# FTDI.net
KiCad netlist of a schematic drawn in Altium Designer
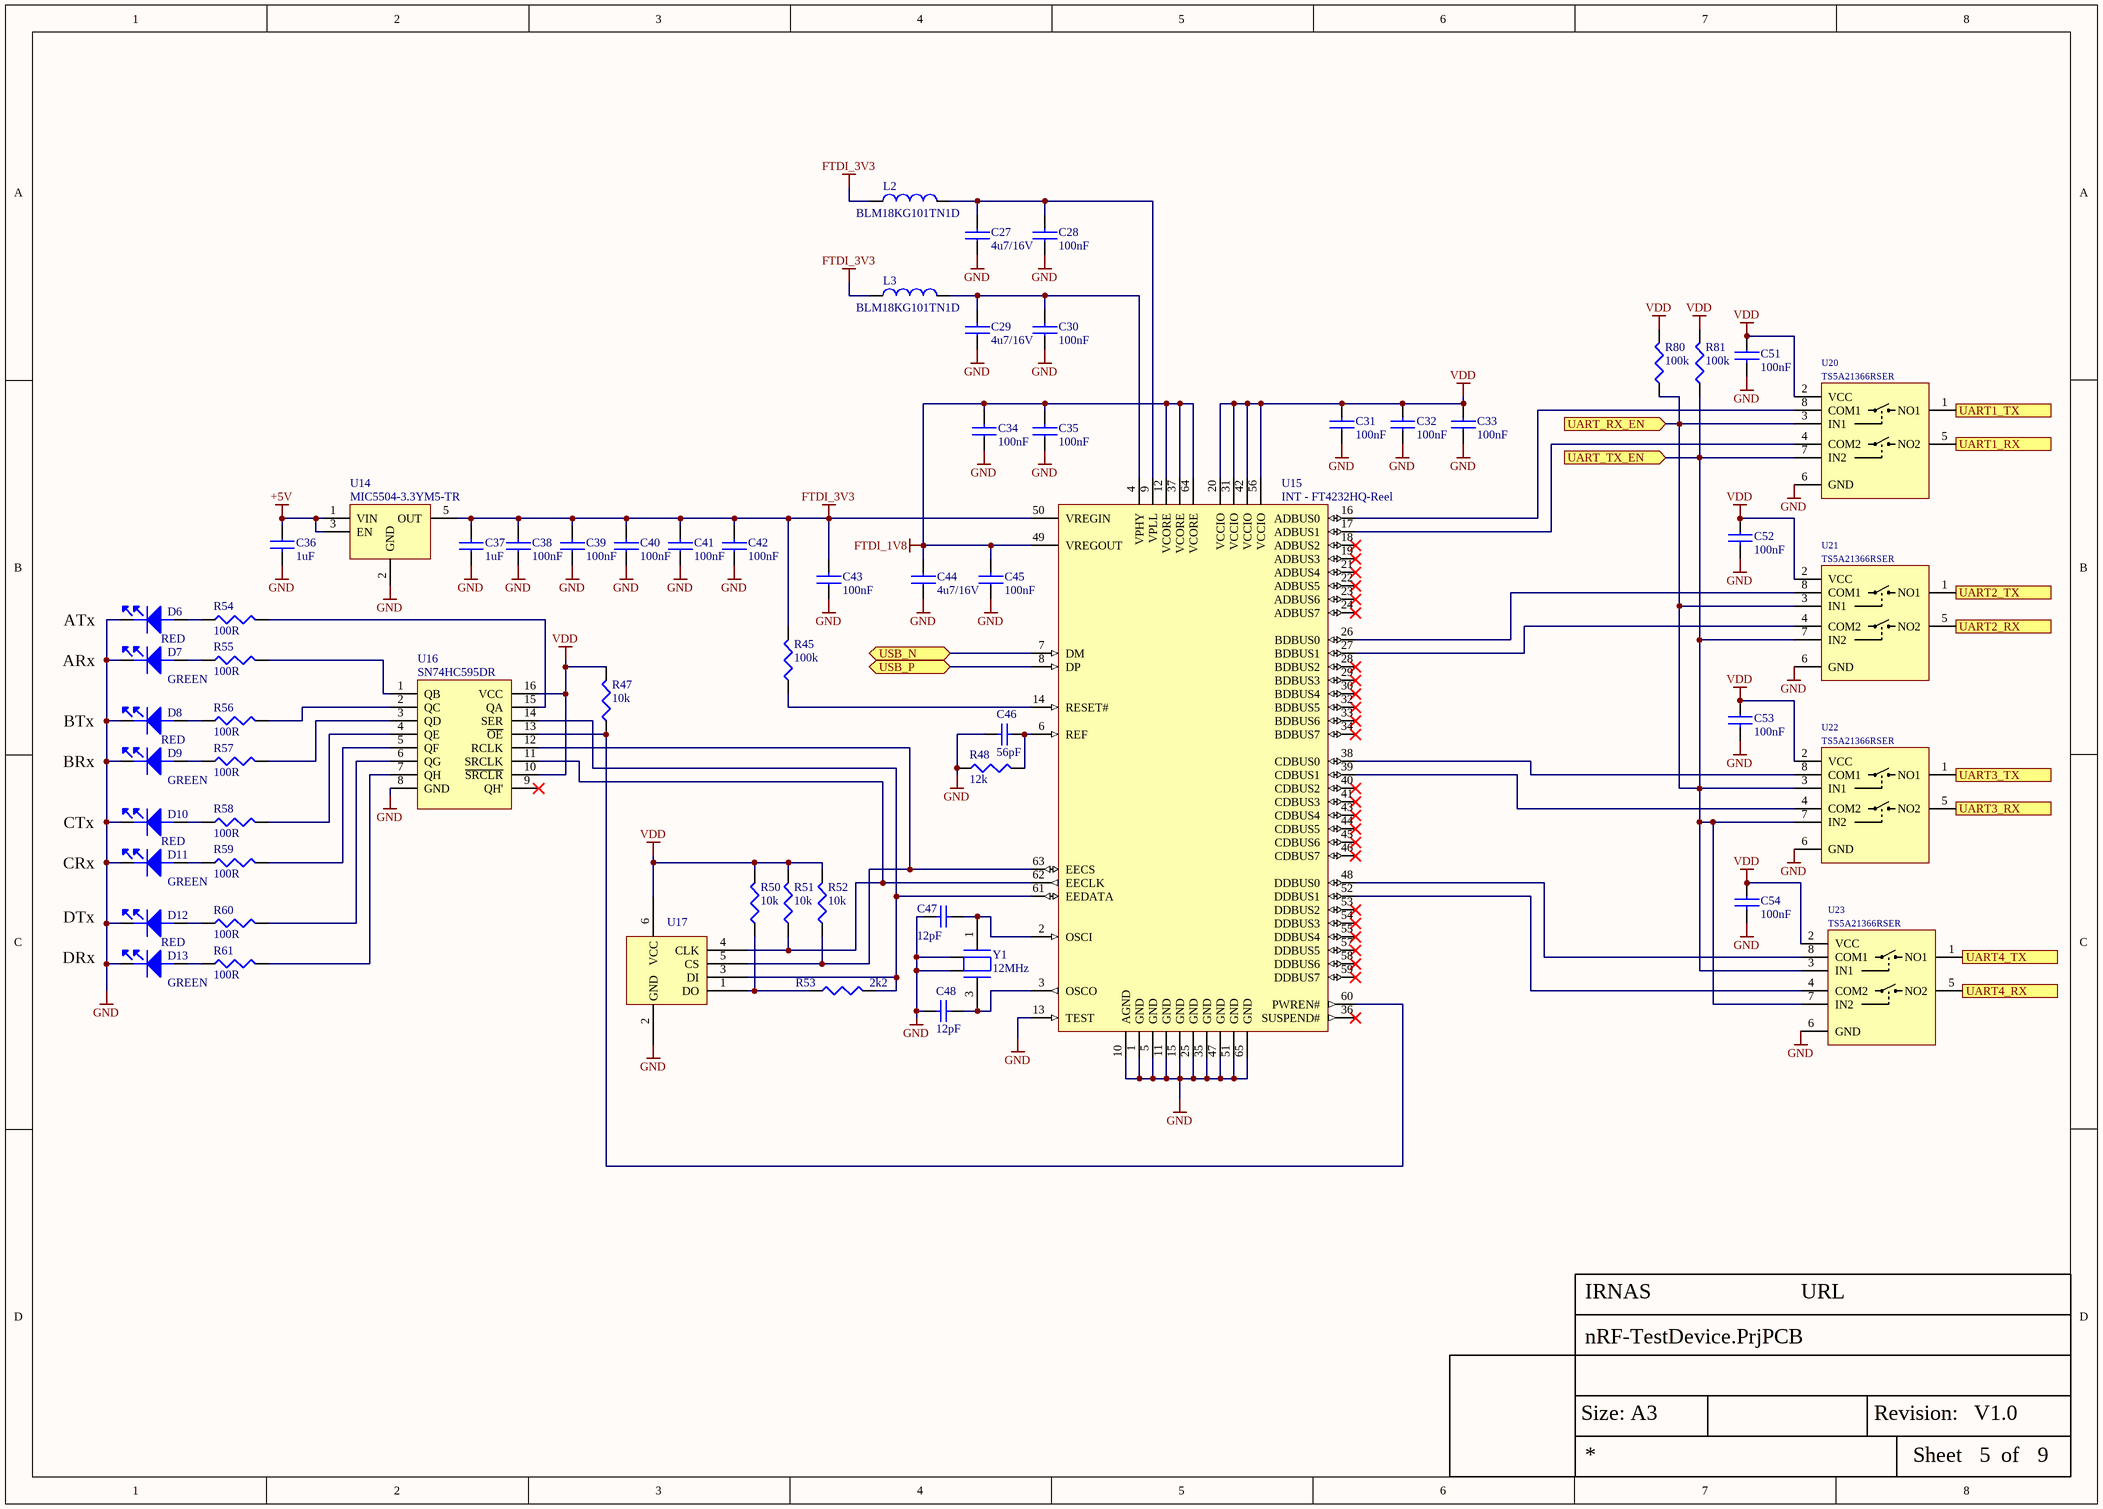
[diagram p0: FTDI.SchDoc]

(export (version "E")
  (design (tool "Eeschema 10.0.6"))
  (components
    (comp (ref "C27")
      (value "4u7/16V")
      (footprint "CAP0603")
      (description "MURATA - GRM188R61C475KAAJD - CAP, MLCC, X5R, 4.7UF, 16V, 0603")
      (fields
        (field (name "MANUFACTURER") "MURATA")
        (field (name "MANUFACTURER PART NUMBER") "GRM188R61C475KAAJD")
      )
      (libsource (lib "Passive") (part "C - 4u7  16V 0603"))
    )
    (comp (ref "C28")
      (value "100nF")
      (footprint "CAP0402")
      (fields
        (field (name "MANUFACTURER") "Multicomp")
        (field (name "MANUFACTURER PART NUMBER") "MC0402X104J160CT")
        (field (name "TOLERANCE") "5%")
      )
      (libsource (lib "Passive") (part "C - 100nF/0402"))
    )
    (comp (ref "C29")
      (value "4u7/16V")
      (footprint "CAP0603")
      (description "MURATA - GRM188R61C475KAAJD - CAP, MLCC, X5R, 4.7UF, 16V, 0603")
      (fields
        (field (name "MANUFACTURER") "MURATA")
        (field (name "MANUFACTURER PART NUMBER") "GRM188R61C475KAAJD")
      )
      (libsource (lib "Passive") (part "C - 4u7  16V 0603"))
    )
    (comp (ref "C30")
      (value "100nF")
      (footprint "CAP0402")
      (fields
        (field (name "MANUFACTURER") "Multicomp")
        (field (name "MANUFACTURER PART NUMBER") "MC0402X104J160CT")
        (field (name "TOLERANCE") "5%")
      )
      (libsource (lib "Passive") (part "C - 100nF/0402"))
    )
    (comp (ref "C31")
      (value "100nF")
      (footprint "CAP0402")
      (fields
        (field (name "MANUFACTURER") "Multicomp")
        (field (name "MANUFACTURER PART NUMBER") "MC0402X104J160CT")
        (field (name "TOLERANCE") "5%")
      )
      (libsource (lib "Passive") (part "C - 100nF/0402"))
    )
    (comp (ref "C32")
      (value "100nF")
      (footprint "CAP0402")
      (fields
        (field (name "MANUFACTURER") "Multicomp")
        (field (name "MANUFACTURER PART NUMBER") "MC0402X104J160CT")
        (field (name "TOLERANCE") "5%")
      )
      (libsource (lib "Passive") (part "C - 100nF/0402"))
    )
    (comp (ref "C33")
      (value "100nF")
      (footprint "CAP0402")
      (fields
        (field (name "MANUFACTURER") "Multicomp")
        (field (name "MANUFACTURER PART NUMBER") "MC0402X104J160CT")
        (field (name "TOLERANCE") "5%")
      )
      (libsource (lib "Passive") (part "C - 100nF/0402"))
    )
    (comp (ref "C34")
      (value "100nF")
      (footprint "CAP0402")
      (fields
        (field (name "MANUFACTURER") "Multicomp")
        (field (name "MANUFACTURER PART NUMBER") "MC0402X104J160CT")
        (field (name "TOLERANCE") "5%")
      )
      (libsource (lib "Passive") (part "C - 100nF/0402"))
    )
    (comp (ref "C35")
      (value "100nF")
      (footprint "CAP0402")
      (fields
        (field (name "MANUFACTURER") "Multicomp")
        (field (name "MANUFACTURER PART NUMBER") "MC0402X104J160CT")
        (field (name "TOLERANCE") "5%")
      )
      (libsource (lib "Passive") (part "C - 100nF/0402"))
    )
    (comp (ref "C36")
      (value "1uF")
      (footprint "CAP0402")
      (description "CAP CER 1UF 10V 20% X5R 0402")
      (fields
        (field (name "MANUFACTURER") "Murata")
        (field (name "MANUFACTURER PART NUMBER") "GRM155R61A105ME15D")
      )
      (libsource (lib "Passive") (part "C - 1uF/0402"))
    )
    (comp (ref "C37")
      (value "1uF")
      (footprint "CAP0402")
      (description "CAP CER 1UF 10V 20% X5R 0402")
      (fields
        (field (name "MANUFACTURER") "Murata")
        (field (name "MANUFACTURER PART NUMBER") "GRM155R61A105ME15D")
      )
      (libsource (lib "Passive") (part "C - 1uF/0402"))
    )
    (comp (ref "C38")
      (value "100nF")
      (footprint "CAP0402")
      (fields
        (field (name "MANUFACTURER") "Multicomp")
        (field (name "MANUFACTURER PART NUMBER") "MC0402X104J160CT")
        (field (name "TOLERANCE") "5%")
      )
      (libsource (lib "Passive") (part "C - 100nF/0402"))
    )
    (comp (ref "C39")
      (value "100nF")
      (footprint "CAP0402")
      (fields
        (field (name "MANUFACTURER") "Multicomp")
        (field (name "MANUFACTURER PART NUMBER") "MC0402X104J160CT")
        (field (name "TOLERANCE") "5%")
      )
      (libsource (lib "Passive") (part "C - 100nF/0402"))
    )
    (comp (ref "C40")
      (value "100nF")
      (footprint "CAP0402")
      (fields
        (field (name "MANUFACTURER") "Multicomp")
        (field (name "MANUFACTURER PART NUMBER") "MC0402X104J160CT")
        (field (name "TOLERANCE") "5%")
      )
      (libsource (lib "Passive") (part "C - 100nF/0402"))
    )
    (comp (ref "C41")
      (value "100nF")
      (footprint "CAP0402")
      (fields
        (field (name "MANUFACTURER") "Multicomp")
        (field (name "MANUFACTURER PART NUMBER") "MC0402X104J160CT")
        (field (name "TOLERANCE") "5%")
      )
      (libsource (lib "Passive") (part "C - 100nF/0402"))
    )
    (comp (ref "C42")
      (value "100nF")
      (footprint "CAP0402")
      (fields
        (field (name "MANUFACTURER") "Multicomp")
        (field (name "MANUFACTURER PART NUMBER") "MC0402X104J160CT")
        (field (name "TOLERANCE") "5%")
      )
      (libsource (lib "Passive") (part "C - 100nF/0402"))
    )
    (comp (ref "C43")
      (value "100nF")
      (footprint "CAP0402")
      (fields
        (field (name "MANUFACTURER") "Multicomp")
        (field (name "MANUFACTURER PART NUMBER") "MC0402X104J160CT")
        (field (name "TOLERANCE") "5%")
      )
      (libsource (lib "Passive") (part "C - 100nF/0402"))
    )
    (comp (ref "C44")
      (value "4u7/16V")
      (footprint "CAP0603")
      (description "MURATA - GRM188R61C475KAAJD - CAP, MLCC, X5R, 4.7UF, 16V, 0603")
      (fields
        (field (name "MANUFACTURER") "MURATA")
        (field (name "MANUFACTURER PART NUMBER") "GRM188R61C475KAAJD")
      )
      (libsource (lib "Passive") (part "C - 4u7  16V 0603"))
    )
    (comp (ref "C45")
      (value "100nF")
      (footprint "CAP0402")
      (fields
        (field (name "MANUFACTURER") "Multicomp")
        (field (name "MANUFACTURER PART NUMBER") "MC0402X104J160CT")
        (field (name "TOLERANCE") "5%")
      )
      (libsource (lib "Passive") (part "C - 100nF/0402"))
    )
    (comp (ref "C46")
      (value "56pF")
      (footprint "CAP0402")
      (description "CAP CER 56PF 50V C0G/NP0 0402")
      (fields (field (name "Comment") "56pF/50V/0402") (field (name "PUBLISHER") "Altium Limited"))
      (libsource (lib "Passive") (part "C - 56pF/50V/0402"))
    )
    (comp (ref "C47")
      (value "12pF")
      (footprint "CAP0402")
      (description "CAP CER 12PF 50V C0G/NP0 0402")
      (fields (field (name "Comment") "12pF/50V/0402") (field (name "PUBLISHER") "Altium Limited"))
      (libsource (lib "Passive") (part "C - 12pF/50V/0402"))
    )
    (comp (ref "C48")
      (value "12pF")
      (footprint "CAP0402")
      (description "CAP CER 12PF 50V C0G/NP0 0402")
      (fields (field (name "Comment") "12pF/50V/0402") (field (name "PUBLISHER") "Altium Limited"))
      (libsource (lib "Passive") (part "C - 12pF/50V/0402"))
    )
    (comp (ref "C51")
      (value "100nF")
      (footprint "CAP0402")
      (fields
        (field (name "MANUFACTURER") "Multicomp")
        (field (name "MANUFACTURER PART NUMBER") "MC0402X104J160CT")
        (field (name "TOLERANCE") "5%")
      )
      (libsource (lib "Passive") (part "C - 100nF/0402"))
    )
    (comp (ref "C52")
      (value "100nF")
      (footprint "CAP0402")
      (fields
        (field (name "MANUFACTURER") "Multicomp")
        (field (name "MANUFACTURER PART NUMBER") "MC0402X104J160CT")
        (field (name "TOLERANCE") "5%")
      )
      (libsource (lib "Passive") (part "C - 100nF/0402"))
    )
    (comp (ref "C53")
      (value "100nF")
      (footprint "CAP0402")
      (fields
        (field (name "MANUFACTURER") "Multicomp")
        (field (name "MANUFACTURER PART NUMBER") "MC0402X104J160CT")
        (field (name "TOLERANCE") "5%")
      )
      (libsource (lib "Passive") (part "C - 100nF/0402"))
    )
    (comp (ref "C54")
      (value "100nF")
      (footprint "CAP0402")
      (fields
        (field (name "MANUFACTURER") "Multicomp")
        (field (name "MANUFACTURER PART NUMBER") "MC0402X104J160CT")
        (field (name "TOLERANCE") "5%")
      )
      (libsource (lib "Passive") (part "C - 100nF/0402"))
    )
    (comp (ref "D6")
      (value "LED RED")
      (footprint "LED0603")
      (description "BROADCOM LIMITED - HSMS-C190 - LED, RED, 10MCD, 626NM")
      (fields
        (field (name "MANUFACTURER") "BROADCOM LIMITED")
        (field (name "MANUFACTURER PART NUMBER") "HSMS-C190")
      )
      (libsource (lib "Active") (part "LED - LED RED"))
    )
    (comp (ref "D7")
      (value "LED GREEN")
      (footprint "LED0603")
      (description "HSME-C191 -  LED, Green, SMD, 0603, 20 mA, 2.1 V, 572 nm")
      (fields
        (field (name "MANUFACTURER") "BROADCOM LIMITED")
        (field (name "MANUFACTURER PART NUMBER") "HSMS-C190")
      )
      (libsource (lib "Active") (part "LED - LED GREEN"))
    )
    (comp (ref "D8")
      (value "LED RED")
      (footprint "LED0603")
      (description "BROADCOM LIMITED - HSMS-C190 - LED, RED, 10MCD, 626NM")
      (fields
        (field (name "MANUFACTURER") "BROADCOM LIMITED")
        (field (name "MANUFACTURER PART NUMBER") "HSMS-C190")
      )
      (libsource (lib "Active") (part "LED - LED RED"))
    )
    (comp (ref "D9")
      (value "LED GREEN")
      (footprint "LED0603")
      (description "HSME-C191 -  LED, Green, SMD, 0603, 20 mA, 2.1 V, 572 nm")
      (fields
        (field (name "MANUFACTURER") "BROADCOM LIMITED")
        (field (name "MANUFACTURER PART NUMBER") "HSMS-C190")
      )
      (libsource (lib "Active") (part "LED - LED GREEN"))
    )
    (comp (ref "D10")
      (value "LED RED")
      (footprint "LED0603")
      (description "BROADCOM LIMITED - HSMS-C190 - LED, RED, 10MCD, 626NM")
      (fields
        (field (name "MANUFACTURER") "BROADCOM LIMITED")
        (field (name "MANUFACTURER PART NUMBER") "HSMS-C190")
      )
      (libsource (lib "Active") (part "LED - LED RED"))
    )
    (comp (ref "D11")
      (value "LED GREEN")
      (footprint "LED0603")
      (description "HSME-C191 -  LED, Green, SMD, 0603, 20 mA, 2.1 V, 572 nm")
      (fields
        (field (name "MANUFACTURER") "BROADCOM LIMITED")
        (field (name "MANUFACTURER PART NUMBER") "HSMS-C190")
      )
      (libsource (lib "Active") (part "LED - LED GREEN"))
    )
    (comp (ref "D12")
      (value "LED RED")
      (footprint "LED0603")
      (description "BROADCOM LIMITED - HSMS-C190 - LED, RED, 10MCD, 626NM")
      (fields
        (field (name "MANUFACTURER") "BROADCOM LIMITED")
        (field (name "MANUFACTURER PART NUMBER") "HSMS-C190")
      )
      (libsource (lib "Active") (part "LED - LED RED"))
    )
    (comp (ref "D13")
      (value "LED GREEN")
      (footprint "LED0603")
      (description "HSME-C191 -  LED, Green, SMD, 0603, 20 mA, 2.1 V, 572 nm")
      (fields
        (field (name "MANUFACTURER") "BROADCOM LIMITED")
        (field (name "MANUFACTURER PART NUMBER") "HSMS-C190")
      )
      (libsource (lib "Active") (part "LED - LED GREEN"))
    )
    (comp (ref "L2")
      (value "BLM18KG101TN1D")
      (footprint "IND0603")
      (description "Ferrite Bead, 0603 [1608 Metric], 100 ohm, 3 A, BLM18K Series, 0.03 ohm, ± 25%")
      (libsource (lib "Passive") (part "L - BLM18KG101TN1D"))
    )
    (comp (ref "L3")
      (value "BLM18KG101TN1D")
      (footprint "IND0603")
      (description "Ferrite Bead, 0603 [1608 Metric], 100 ohm, 3 A, BLM18K Series, 0.03 ohm, ± 25%")
      (libsource (lib "Passive") (part "L - BLM18KG101TN1D"))
    )
    (comp (ref "R45")
      (value "100k")
      (footprint "RES0402")
      (description "MULTICOMP   MCWR04X1003FTL   RES, THICK FILM, 100KOHM, 1%, 0.0625W")
      (fields
        (field (name "MANUFACTURER") "Multicomp")
        (field (name "MANUFACTURER PART NUMBER") "MCWR04X1003FTL")
      )
      (libsource (lib "Passive") (part "R - 100k/0402"))
    )
    (comp (ref "R47")
      (value "10k")
      (footprint "RES0402")
      (fields
        (field (name "MANUFACTURER") "Multicomp")
        (field (name "MANUFACTURER PART NUMBER") "MCWR04X1002FTL")
        (field (name "TOLERANCE") "1%")
      )
      (libsource (lib "Passive") (part "R - 10k/0402"))
    )
    (comp (ref "R48")
      (value "12k")
      (footprint "RES0402")
      (fields
        (field (name "MANUFACTURER") "Multicomp")
        (field (name "MANUFACTURER PART NUMBER") "MCWR04X1202FTL")
        (field (name "TOLERANCE") "1%")
      )
      (libsource (lib "Passive") (part "R - 12k/0402"))
    )
    (comp (ref "R50")
      (value "10k")
      (footprint "RES0402")
      (fields
        (field (name "MANUFACTURER") "Multicomp")
        (field (name "MANUFACTURER PART NUMBER") "MCWR04X1002FTL")
        (field (name "TOLERANCE") "1%")
      )
      (libsource (lib "Passive") (part "R - 10k/0402"))
    )
    (comp (ref "R51")
      (value "10k")
      (footprint "RES0402")
      (fields
        (field (name "MANUFACTURER") "Multicomp")
        (field (name "MANUFACTURER PART NUMBER") "MCWR04X1002FTL")
        (field (name "TOLERANCE") "1%")
      )
      (libsource (lib "Passive") (part "R - 10k/0402"))
    )
    (comp (ref "R52")
      (value "10k")
      (footprint "RES0402")
      (fields
        (field (name "MANUFACTURER") "Multicomp")
        (field (name "MANUFACTURER PART NUMBER") "MCWR04X1002FTL")
        (field (name "TOLERANCE") "1%")
      )
      (libsource (lib "Passive") (part "R - 10k/0402"))
    )
    (comp (ref "R53")
      (value "2k2")
      (footprint "RES0402")
      (description "SMD Chip Resistor, 2.2 kohm, ± 1%, 62.5 mW, 0402 [1005 Metric], Thick Film, General Purpose")
      (libsource (lib "Passive") (part "R - 2k2/0402"))
    )
    (comp (ref "R54")
      (value "100R")
      (footprint "RES0402")
      (fields
        (field (name "MANUFACTURER") "Multicomp")
        (field (name "MANUFACTURER PART NUMBER") "MCMR04X1000FTL")
        (field (name "TOLERANCE") "1%")
      )
      (libsource (lib "Passive") (part "R - 100R/0402"))
    )
    (comp (ref "R55")
      (value "100R")
      (footprint "RES0402")
      (fields
        (field (name "MANUFACTURER") "Multicomp")
        (field (name "MANUFACTURER PART NUMBER") "MCMR04X1000FTL")
        (field (name "TOLERANCE") "1%")
      )
      (libsource (lib "Passive") (part "R - 100R/0402"))
    )
    (comp (ref "R56")
      (value "100R")
      (footprint "RES0402")
      (fields
        (field (name "MANUFACTURER") "Multicomp")
        (field (name "MANUFACTURER PART NUMBER") "MCMR04X1000FTL")
        (field (name "TOLERANCE") "1%")
      )
      (libsource (lib "Passive") (part "R - 100R/0402"))
    )
    (comp (ref "R57")
      (value "100R")
      (footprint "RES0402")
      (fields
        (field (name "MANUFACTURER") "Multicomp")
        (field (name "MANUFACTURER PART NUMBER") "MCMR04X1000FTL")
        (field (name "TOLERANCE") "1%")
      )
      (libsource (lib "Passive") (part "R - 100R/0402"))
    )
    (comp (ref "R58")
      (value "100R")
      (footprint "RES0402")
      (fields
        (field (name "MANUFACTURER") "Multicomp")
        (field (name "MANUFACTURER PART NUMBER") "MCMR04X1000FTL")
        (field (name "TOLERANCE") "1%")
      )
      (libsource (lib "Passive") (part "R - 100R/0402"))
    )
    (comp (ref "R59")
      (value "100R")
      (footprint "RES0402")
      (fields
        (field (name "MANUFACTURER") "Multicomp")
        (field (name "MANUFACTURER PART NUMBER") "MCMR04X1000FTL")
        (field (name "TOLERANCE") "1%")
      )
      (libsource (lib "Passive") (part "R - 100R/0402"))
    )
    (comp (ref "R60")
      (value "100R")
      (footprint "RES0402")
      (fields
        (field (name "MANUFACTURER") "Multicomp")
        (field (name "MANUFACTURER PART NUMBER") "MCMR04X1000FTL")
        (field (name "TOLERANCE") "1%")
      )
      (libsource (lib "Passive") (part "R - 100R/0402"))
    )
    (comp (ref "R61")
      (value "100R")
      (footprint "RES0402")
      (fields
        (field (name "MANUFACTURER") "Multicomp")
        (field (name "MANUFACTURER PART NUMBER") "MCMR04X1000FTL")
        (field (name "TOLERANCE") "1%")
      )
      (libsource (lib "Passive") (part "R - 100R/0402"))
    )
    (comp (ref "R80")
      (value "100k")
      (footprint "RES0402")
      (description "MULTICOMP   MCWR04X1003FTL   RES, THICK FILM, 100KOHM, 1%, 0.0625W")
      (fields
        (field (name "MANUFACTURER") "Multicomp")
        (field (name "MANUFACTURER PART NUMBER") "MCWR04X1003FTL")
      )
      (libsource (lib "Passive") (part "R - 100k/0402"))
    )
    (comp (ref "R81")
      (value "100k")
      (footprint "RES0402")
      (description "MULTICOMP   MCWR04X1003FTL   RES, THICK FILM, 100KOHM, 1%, 0.0625W")
      (fields
        (field (name "MANUFACTURER") "Multicomp")
        (field (name "MANUFACTURER PART NUMBER") "MCWR04X1003FTL")
      )
      (libsource (lib "Passive") (part "R - 100k/0402"))
    )
    (comp (ref "U14")
      (value "MIC5504-3.3YM5-TR")
      (footprint "SOT23-5")
      (description "Fixed LDO Voltage Regulator, 2.5V to 5.5V, 160mV Dropout, 3.3Vout, 300mAout, SOT-23-5")
      (fields
        (field (name "MANUFACTURER") "ON SEMICONDUCTOR")
        (field (name "MANUFACTURER PART NUMBER") "LM2596DSADJG")
      )
      (libsource (lib "Active") (part "V_LIN - MIC5504-3.3YM5-TR"))
    )
    (comp (ref "U15")
      (value "INT - FT4232HQ-Reel")
      (footprint "QFN64_2_N")
      (description "Quad High Speed USB To Multipurpose UART/MPSSE IC, 64-pin QFN, Tape and Reel")
      (fields (field (name "MANUFACTURER") "FTDI") (field (name "PARTNUMBER") "FT4232HQ-Reel"))
      (libsource (lib "Active") (part "INT - FT4232HQ-Reel"))
    )
    (comp (ref "U16")
      (value "SN74HC595DR")
      (footprint "SOIC-16")
      (description "Shift Register, 74HC595, Serial to Parallel, 1 Element, 8 bit, SOIC, 16 Pins")
      (libsource (lib "Active") (part "INT - SN74HC595DR"))
    )
    (comp (ref "U17")
      (value "93LC56BT-E/OT")
      (footprint "SOT95P270X145-6N")
      (description "2K,  128 X 16,  SERIAL EE,   EXT6 SOT-23  T/R")
      (fields (field (name "MANUFACTURER") "Microchip"))
      (libsource (lib "Active") (part "MEM - 93LC56BT-E/OT"))
    )
    (comp (ref "U20")
      (value "TS5A21366RSER")
      (footprint "UQFN-8")
      (description "IC SWITCH DUAL SPST 8QFN")
      (libsource (lib "Active") (part "SW - TS5A21366RSER"))
    )
    (comp (ref "U21")
      (value "TS5A21366RSER")
      (footprint "UQFN-8")
      (description "IC SWITCH DUAL SPST 8QFN")
      (libsource (lib "Active") (part "SW - TS5A21366RSER"))
    )
    (comp (ref "U22")
      (value "TS5A21366RSER")
      (footprint "UQFN-8")
      (description "IC SWITCH DUAL SPST 8QFN")
      (libsource (lib "Active") (part "SW - TS5A21366RSER"))
    )
    (comp (ref "U23")
      (value "TS5A21366RSER")
      (footprint "UQFN-8")
      (description "IC SWITCH DUAL SPST 8QFN")
      (libsource (lib "Active") (part "SW - TS5A21366RSER"))
    )
    (comp (ref "Y1")
      (value "12MHz")
      (footprint "CRY2.5X2")
      (description "12MHz ±20ppm Crystal 10pF 150 Ohm -40°C ~ 85°C  Surface Mount 4-SMD, No Lead (DFN, LCC)")
      (fields
        (field (name "MANUFACTURER") "Abracon")
        (field (name "MANUFACTURER PART NUMBER") "ABM10-166-12.000MHZ-T3")
      )
      (libsource (lib "Passive") (part "X - 16MHz"))
    )
  )
  (nets
    (net (code "1") (name "+5V") (class "Default")
      (node (ref "C36") (pin "1") (pinfunction "1_1") (pintype "passive"))
      (node (ref "U14") (pin "1") (pinfunction "VIN_1") (pintype "open_collector"))
      (node (ref "U14") (pin "3") (pinfunction "EN_3") (pintype "open_collector"))
    )
    (net (code "2") (name "/UART1_RX") (class "Default")
      (node (ref "U20") (pin "5") (pinfunction "NO2_5") (pintype "passive"))
    )
    (net (code "3") (name "/UART1_TX") (class "Default")
      (node (ref "U20") (pin "1") (pinfunction "NO1_1") (pintype "passive"))
    )
    (net (code "4") (name "/UART2_RX") (class "Default")
      (node (ref "U21") (pin "5") (pinfunction "NO2_5") (pintype "passive"))
    )
    (net (code "5") (name "/UART2_TX") (class "Default")
      (node (ref "U21") (pin "1") (pinfunction "NO1_1") (pintype "passive"))
    )
    (net (code "6") (name "/UART3_RX") (class "Default")
      (node (ref "U22") (pin "5") (pinfunction "NO2_5") (pintype "passive"))
    )
    (net (code "7") (name "/UART3_TX") (class "Default")
      (node (ref "U22") (pin "1") (pinfunction "NO1_1") (pintype "passive"))
    )
    (net (code "8") (name "/UART4_RX") (class "Default")
      (node (ref "U23") (pin "5") (pinfunction "NO2_5") (pintype "passive"))
    )
    (net (code "9") (name "/UART4_TX") (class "Default")
      (node (ref "U23") (pin "1") (pinfunction "NO1_1") (pintype "passive"))
    )
    (net (code "10") (name "/UART_RX_EN") (class "Default")
      (node (ref "R80") (pin "1") (pinfunction "1_1") (pintype "passive"))
      (node (ref "R81") (pin "1") (pinfunction "1_1") (pintype "passive"))
      (node (ref "U20") (pin "3") (pinfunction "IN1_3") (pintype "passive"))
      (node (ref "U20") (pin "7") (pinfunction "IN2_7") (pintype "passive"))
      (node (ref "U21") (pin "3") (pinfunction "IN1_3") (pintype "passive"))
      (node (ref "U21") (pin "7") (pinfunction "IN2_7") (pintype "passive"))
      (node (ref "U22") (pin "3") (pinfunction "IN1_3") (pintype "passive"))
      (node (ref "U22") (pin "7") (pinfunction "IN2_7") (pintype "passive"))
      (node (ref "U23") (pin "3") (pinfunction "IN1_3") (pintype "passive"))
      (node (ref "U23") (pin "7") (pinfunction "IN2_7") (pintype "passive"))
    )
    (net (code "11") (name "/USB_N") (class "Default")
      (node (ref "U15") (pin "7") (pinfunction "DM_7") (pintype "input"))
    )
    (net (code "12") (name "/USB_P") (class "Default")
      (node (ref "U15") (pin "8") (pinfunction "DP_8") (pintype "input"))
    )
    (net (code "13") (name "FTDI_1V8") (class "Default")
      (node (ref "C34") (pin "2") (pinfunction "2_2") (pintype "passive"))
      (node (ref "C35") (pin "2") (pinfunction "2_2") (pintype "passive"))
      (node (ref "C44") (pin "2") (pinfunction "2_2") (pintype "passive"))
      (node (ref "C45") (pin "2") (pinfunction "2_2") (pintype "passive"))
      (node (ref "U15") (pin "12") (pinfunction "VCORE_12") (pintype "power_in"))
      (node (ref "U15") (pin "37") (pinfunction "VCORE_37") (pintype "power_in"))
      (node (ref "U15") (pin "49") (pinfunction "VREGOUT_49") (pintype "power_in"))
      (node (ref "U15") (pin "64") (pinfunction "VCORE_64") (pintype "power_in"))
    )
    (net (code "14") (name "FTDI_3V3") (class "Default")
      (node (ref "C37") (pin "2") (pinfunction "2_2") (pintype "passive"))
      (node (ref "C38") (pin "2") (pinfunction "2_2") (pintype "passive"))
      (node (ref "C39") (pin "2") (pinfunction "2_2") (pintype "passive"))
      (node (ref "C40") (pin "2") (pinfunction "2_2") (pintype "passive"))
      (node (ref "C41") (pin "2") (pinfunction "2_2") (pintype "passive"))
      (node (ref "C42") (pin "2") (pinfunction "2_2") (pintype "passive"))
      (node (ref "C43") (pin "2") (pinfunction "2_2") (pintype "passive"))
      (node (ref "L2") (pin "1") (pinfunction "1_1") (pintype "passive"))
      (node (ref "L3") (pin "1") (pinfunction "1_1") (pintype "passive"))
      (node (ref "R45") (pin "2") (pinfunction "2_2") (pintype "passive"))
      (node (ref "U14") (pin "5") (pinfunction "OUT_5") (pintype "power_in"))
      (node (ref "U15") (pin "50") (pinfunction "VREGIN_50") (pintype "power_in"))
    )
    (net (code "15") (name "GND") (class "Default")
      (node (ref "C27") (pin "1") (pinfunction "1_1") (pintype "passive"))
      (node (ref "C28") (pin "1") (pinfunction "1_1") (pintype "passive"))
      (node (ref "C29") (pin "1") (pinfunction "1_1") (pintype "passive"))
      (node (ref "C30") (pin "1") (pinfunction "1_1") (pintype "passive"))
      (node (ref "C31") (pin "1") (pinfunction "1_1") (pintype "passive"))
      (node (ref "C32") (pin "1") (pinfunction "1_1") (pintype "passive"))
      (node (ref "C33") (pin "1") (pinfunction "1_1") (pintype "passive"))
      (node (ref "C34") (pin "1") (pinfunction "1_1") (pintype "passive"))
      (node (ref "C35") (pin "1") (pinfunction "1_1") (pintype "passive"))
      (node (ref "C36") (pin "2") (pinfunction "2_2") (pintype "passive"))
      (node (ref "C37") (pin "1") (pinfunction "1_1") (pintype "passive"))
      (node (ref "C38") (pin "1") (pinfunction "1_1") (pintype "passive"))
      (node (ref "C39") (pin "1") (pinfunction "1_1") (pintype "passive"))
      (node (ref "C40") (pin "1") (pinfunction "1_1") (pintype "passive"))
      (node (ref "C41") (pin "1") (pinfunction "1_1") (pintype "passive"))
      (node (ref "C42") (pin "1") (pinfunction "1_1") (pintype "passive"))
      (node (ref "C43") (pin "1") (pinfunction "1_1") (pintype "passive"))
      (node (ref "C44") (pin "1") (pinfunction "1_1") (pintype "passive"))
      (node (ref "C45") (pin "1") (pinfunction "1_1") (pintype "passive"))
      (node (ref "C46") (pin "1") (pinfunction "1_1") (pintype "passive"))
      (node (ref "C47") (pin "1") (pinfunction "1_1") (pintype "passive"))
      (node (ref "C48") (pin "1") (pinfunction "1_1") (pintype "passive"))
      (node (ref "C51") (pin "2") (pinfunction "2_2") (pintype "passive"))
      (node (ref "C52") (pin "2") (pinfunction "2_2") (pintype "passive"))
      (node (ref "C53") (pin "2") (pinfunction "2_2") (pintype "passive"))
      (node (ref "C54") (pin "2") (pinfunction "2_2") (pintype "passive"))
      (node (ref "D10") (pin "1") (pinfunction "cathode_1") (pintype "passive"))
      (node (ref "D11") (pin "1") (pinfunction "cathode_1") (pintype "passive"))
      (node (ref "D12") (pin "1") (pinfunction "cathode_1") (pintype "passive"))
      (node (ref "D13") (pin "1") (pinfunction "cathode_1") (pintype "passive"))
      (node (ref "D6") (pin "1") (pinfunction "cathode_1") (pintype "passive"))
      (node (ref "D7") (pin "1") (pinfunction "cathode_1") (pintype "passive"))
      (node (ref "D8") (pin "1") (pinfunction "cathode_1") (pintype "passive"))
      (node (ref "D9") (pin "1") (pinfunction "cathode_1") (pintype "passive"))
      (node (ref "R48") (pin "1") (pinfunction "1_1") (pintype "passive"))
      (node (ref "U14") (pin "2") (pinfunction "GND_2") (pintype "passive"))
      (node (ref "U15") (pin "1") (pinfunction "GND_1") (pintype "passive"))
      (node (ref "U15") (pin "10") (pinfunction "AGND_10") (pintype "passive"))
      (node (ref "U15") (pin "11") (pinfunction "GND_11") (pintype "passive"))
      (node (ref "U15") (pin "13") (pinfunction "TEST_13") (pintype "input"))
      (node (ref "U15") (pin "15") (pinfunction "GND_15") (pintype "passive"))
      (node (ref "U15") (pin "25") (pinfunction "GND_25") (pintype "passive"))
      (node (ref "U15") (pin "35") (pinfunction "GND_35") (pintype "passive"))
      (node (ref "U15") (pin "47") (pinfunction "GND_47") (pintype "passive"))
      (node (ref "U15") (pin "5") (pinfunction "GND_5") (pintype "passive"))
      (node (ref "U15") (pin "51") (pinfunction "GND_51") (pintype "passive"))
      (node (ref "U15") (pin "65") (pinfunction "GND_65") (pintype "passive"))
      (node (ref "U16") (pin "8") (pinfunction "GND_8") (pintype "passive"))
      (node (ref "U17") (pin "2") (pinfunction "GND_2") (pintype "passive"))
      (node (ref "U20") (pin "6") (pinfunction "GND_6") (pintype "passive"))
      (node (ref "U21") (pin "6") (pinfunction "GND_6") (pintype "passive"))
      (node (ref "U22") (pin "6") (pinfunction "GND_6") (pintype "passive"))
      (node (ref "U23") (pin "6") (pinfunction "GND_6") (pintype "passive"))
      (node (ref "Y1") (pin "2") (pinfunction "2_2") (pintype "open_collector"))
      (node (ref "Y1") (pin "4") (pinfunction "4_4") (pintype "open_collector"))
    )
    (net (code "16") (name "Net-(D6-ANODE)") (class "Default")
      (node (ref "D6") (pin "2") (pinfunction "ANODE_2") (pintype "passive"))
      (node (ref "R54") (pin "1") (pinfunction "1_1") (pintype "passive"))
    )
    (net (code "17") (name "Net-(D7-ANODE)") (class "Default")
      (node (ref "D7") (pin "2") (pinfunction "ANODE_2") (pintype "passive"))
      (node (ref "R55") (pin "1") (pinfunction "1_1") (pintype "passive"))
    )
    (net (code "18") (name "Net-(D8-ANODE)") (class "Default")
      (node (ref "D8") (pin "2") (pinfunction "ANODE_2") (pintype "passive"))
      (node (ref "R56") (pin "1") (pinfunction "1_1") (pintype "passive"))
    )
    (net (code "19") (name "Net-(D9-ANODE)") (class "Default")
      (node (ref "D9") (pin "2") (pinfunction "ANODE_2") (pintype "passive"))
      (node (ref "R57") (pin "1") (pinfunction "1_1") (pintype "passive"))
    )
    (net (code "20") (name "Net-(D10-ANODE)") (class "Default")
      (node (ref "D10") (pin "2") (pinfunction "ANODE_2") (pintype "passive"))
      (node (ref "R58") (pin "1") (pinfunction "1_1") (pintype "passive"))
    )
    (net (code "21") (name "Net-(D11-ANODE)") (class "Default")
      (node (ref "D11") (pin "2") (pinfunction "ANODE_2") (pintype "passive"))
      (node (ref "R59") (pin "1") (pinfunction "1_1") (pintype "passive"))
    )
    (net (code "22") (name "Net-(D12-ANODE)") (class "Default")
      (node (ref "D12") (pin "2") (pinfunction "ANODE_2") (pintype "passive"))
      (node (ref "R60") (pin "1") (pinfunction "1_1") (pintype "passive"))
    )
    (net (code "23") (name "Net-(D13-ANODE)") (class "Default")
      (node (ref "D13") (pin "2") (pinfunction "ANODE_2") (pintype "passive"))
      (node (ref "R61") (pin "1") (pinfunction "1_1") (pintype "passive"))
    )
    (net (code "24") (name "Net-(U15-ADBUS0)") (class "Default")
      (node (ref "U15") (pin "16") (pinfunction "ADBUS0_16") (pintype "bidirectional"))
      (node (ref "U20") (pin "8") (pinfunction "COM1_8") (pintype "passive"))
    )
    (net (code "25") (name "Net-(U15-ADBUS1)") (class "Default")
      (node (ref "U15") (pin "17") (pinfunction "ADBUS1_17") (pintype "bidirectional"))
      (node (ref "U20") (pin "4") (pinfunction "COM2_4") (pintype "passive"))
    )
    (net (code "26") (name "Net-(U15-BDBUS0)") (class "Default")
      (node (ref "U15") (pin "26") (pinfunction "BDBUS0_26") (pintype "bidirectional"))
      (node (ref "U21") (pin "8") (pinfunction "COM1_8") (pintype "passive"))
    )
    (net (code "27") (name "Net-(U15-BDBUS1)") (class "Default")
      (node (ref "U15") (pin "27") (pinfunction "BDBUS1_27") (pintype "bidirectional"))
      (node (ref "U21") (pin "4") (pinfunction "COM2_4") (pintype "passive"))
    )
    (net (code "28") (name "Net-(U15-CDBUS0)") (class "Default")
      (node (ref "U15") (pin "38") (pinfunction "CDBUS0_38") (pintype "bidirectional"))
      (node (ref "U22") (pin "8") (pinfunction "COM1_8") (pintype "passive"))
    )
    (net (code "29") (name "Net-(U15-CDBUS1)") (class "Default")
      (node (ref "U15") (pin "39") (pinfunction "CDBUS1_39") (pintype "bidirectional"))
      (node (ref "U22") (pin "4") (pinfunction "COM2_4") (pintype "passive"))
    )
    (net (code "30") (name "Net-(U15-DDBUS0)") (class "Default")
      (node (ref "U15") (pin "48") (pinfunction "DDBUS0_48") (pintype "bidirectional"))
      (node (ref "U23") (pin "8") (pinfunction "COM1_8") (pintype "passive"))
    )
    (net (code "31") (name "Net-(U15-DDBUS1)") (class "Default")
      (node (ref "U15") (pin "52") (pinfunction "DDBUS1_52") (pintype "bidirectional"))
      (node (ref "U23") (pin "4") (pinfunction "COM2_4") (pintype "passive"))
    )
    (net (code "32") (name "Net-(U15-EECLK)") (class "Default")
      (node (ref "R51") (pin "1") (pinfunction "1_1") (pintype "passive"))
      (node (ref "U15") (pin "62") (pinfunction "EECLK_62") (pintype "output"))
      (node (ref "U16") (pin "11") (pinfunction "SRCLK_11") (pintype "passive"))
      (node (ref "U17") (pin "4") (pinfunction "CLK_4") (pintype "passive"))
    )
    (net (code "33") (name "Net-(U15-EECS)") (class "Default")
      (node (ref "R52") (pin "1") (pinfunction "1_1") (pintype "passive"))
      (node (ref "U15") (pin "63") (pinfunction "EECS_63") (pintype "bidirectional"))
      (node (ref "U16") (pin "12") (pinfunction "RCLK_12") (pintype "passive"))
      (node (ref "U17") (pin "5") (pinfunction "CS_5") (pintype "passive"))
    )
    (net (code "34") (name "Net-(U15-EEDATA)") (class "Default")
      (node (ref "R53") (pin "2") (pinfunction "2_2") (pintype "passive"))
      (node (ref "U15") (pin "61") (pinfunction "EEDATA_61") (pintype "bidirectional"))
      (node (ref "U16") (pin "14") (pinfunction "SER_14") (pintype "passive"))
      (node (ref "U17") (pin "3") (pinfunction "DI_3") (pintype "passive"))
    )
    (net (code "35") (name "Net-(U15-OSCI)") (class "Default")
      (node (ref "C47") (pin "2") (pinfunction "2_2") (pintype "passive"))
      (node (ref "U15") (pin "2") (pinfunction "OSCI_2") (pintype "input"))
      (node (ref "Y1") (pin "1") (pinfunction "1_1") (pintype "open_collector"))
    )
    (net (code "36") (name "Net-(U15-OSCO)") (class "Default")
      (node (ref "C48") (pin "2") (pinfunction "2_2") (pintype "passive"))
      (node (ref "U15") (pin "3") (pinfunction "OSCO_3") (pintype "output"))
      (node (ref "Y1") (pin "3") (pinfunction "3_3") (pintype "open_collector"))
    )
    (net (code "37") (name "Net-(U15-PWREN#)") (class "Default")
      (node (ref "R47") (pin "1") (pinfunction "1_1") (pintype "passive"))
      (node (ref "U15") (pin "60") (pinfunction "PWREN#_60") (pintype "output"))
      (node (ref "U16") (pin "13") (pinfunction "~{OE}_13") (pintype "passive"))
    )
    (net (code "38") (name "Net-(U15-REF)") (class "Default")
      (node (ref "C46") (pin "2") (pinfunction "2_2") (pintype "passive"))
      (node (ref "R48") (pin "2") (pinfunction "2_2") (pintype "passive"))
      (node (ref "U15") (pin "6") (pinfunction "REF_6") (pintype "input"))
    )
    (net (code "39") (name "Net-(U15-RESET#)") (class "Default")
      (node (ref "R45") (pin "1") (pinfunction "1_1") (pintype "passive"))
      (node (ref "U15") (pin "14") (pinfunction "RESET#_14") (pintype "input"))
    )
    (net (code "40") (name "Net-(U15-VPHY)") (class "Default")
      (node (ref "C29") (pin "2") (pinfunction "2_2") (pintype "passive"))
      (node (ref "C30") (pin "2") (pinfunction "2_2") (pintype "passive"))
      (node (ref "L3") (pin "2") (pinfunction "2_2") (pintype "passive"))
      (node (ref "U15") (pin "4") (pinfunction "VPHY_4") (pintype "power_in"))
    )
    (net (code "41") (name "Net-(U15-VPLL)") (class "Default")
      (node (ref "C27") (pin "2") (pinfunction "2_2") (pintype "passive"))
      (node (ref "C28") (pin "2") (pinfunction "2_2") (pintype "passive"))
      (node (ref "L2") (pin "2") (pinfunction "2_2") (pintype "passive"))
      (node (ref "U15") (pin "9") (pinfunction "VPLL_9") (pintype "power_in"))
    )
    (net (code "42") (name "Net-(U16-QA)") (class "Default")
      (node (ref "R54") (pin "2") (pinfunction "2_2") (pintype "passive"))
      (node (ref "U16") (pin "15") (pinfunction "QA_15") (pintype "passive"))
    )
    (net (code "43") (name "Net-(U16-QB)") (class "Default")
      (node (ref "R55") (pin "2") (pinfunction "2_2") (pintype "passive"))
      (node (ref "U16") (pin "1") (pinfunction "QB_1") (pintype "passive"))
    )
    (net (code "44") (name "Net-(U16-QC)") (class "Default")
      (node (ref "R56") (pin "2") (pinfunction "2_2") (pintype "passive"))
      (node (ref "U16") (pin "2") (pinfunction "QC_2") (pintype "passive"))
    )
    (net (code "45") (name "Net-(U16-QD)") (class "Default")
      (node (ref "R57") (pin "2") (pinfunction "2_2") (pintype "passive"))
      (node (ref "U16") (pin "3") (pinfunction "QD_3") (pintype "passive"))
    )
    (net (code "46") (name "Net-(U16-QE)") (class "Default")
      (node (ref "R58") (pin "2") (pinfunction "2_2") (pintype "passive"))
      (node (ref "U16") (pin "4") (pinfunction "QE_4") (pintype "passive"))
    )
    (net (code "47") (name "Net-(U16-QF)") (class "Default")
      (node (ref "R59") (pin "2") (pinfunction "2_2") (pintype "passive"))
      (node (ref "U16") (pin "5") (pinfunction "QF_5") (pintype "passive"))
    )
    (net (code "48") (name "Net-(U16-QG)") (class "Default")
      (node (ref "R60") (pin "2") (pinfunction "2_2") (pintype "passive"))
      (node (ref "U16") (pin "6") (pinfunction "QG_6") (pintype "passive"))
    )
    (net (code "49") (name "Net-(U16-QH)") (class "Default")
      (node (ref "R61") (pin "2") (pinfunction "2_2") (pintype "passive"))
      (node (ref "U16") (pin "7") (pinfunction "QH_7") (pintype "passive"))
    )
    (net (code "50") (name "Net-(U17-DO)") (class "Default")
      (node (ref "R50") (pin "1") (pinfunction "1_1") (pintype "passive"))
      (node (ref "R53") (pin "1") (pinfunction "1_1") (pintype "passive"))
      (node (ref "U17") (pin "1") (pinfunction "DO_1") (pintype "passive"))
    )
    (net (code "51") (name "VDD") (class "Default")
      (node (ref "C31") (pin "2") (pinfunction "2_2") (pintype "passive"))
      (node (ref "C32") (pin "2") (pinfunction "2_2") (pintype "passive"))
      (node (ref "C33") (pin "2") (pinfunction "2_2") (pintype "passive"))
      (node (ref "C51") (pin "1") (pinfunction "1_1") (pintype "passive"))
      (node (ref "C52") (pin "1") (pinfunction "1_1") (pintype "passive"))
      (node (ref "C53") (pin "1") (pinfunction "1_1") (pintype "passive"))
      (node (ref "C54") (pin "1") (pinfunction "1_1") (pintype "passive"))
      (node (ref "R47") (pin "2") (pinfunction "2_2") (pintype "passive"))
      (node (ref "R50") (pin "2") (pinfunction "2_2") (pintype "passive"))
      (node (ref "R51") (pin "2") (pinfunction "2_2") (pintype "passive"))
      (node (ref "R52") (pin "2") (pinfunction "2_2") (pintype "passive"))
      (node (ref "R80") (pin "2") (pinfunction "2_2") (pintype "passive"))
      (node (ref "R81") (pin "2") (pinfunction "2_2") (pintype "passive"))
      (node (ref "U15") (pin "20") (pinfunction "VCCIO_20") (pintype "power_in"))
      (node (ref "U15") (pin "31") (pinfunction "VCCIO_31") (pintype "power_in"))
      (node (ref "U15") (pin "42") (pinfunction "VCCIO_42") (pintype "power_in"))
      (node (ref "U15") (pin "56") (pinfunction "VCCIO_56") (pintype "power_in"))
      (node (ref "U16") (pin "10") (pinfunction "~{SRCLR}_10") (pintype "passive"))
      (node (ref "U16") (pin "16") (pinfunction "VCC_16") (pintype "passive"))
      (node (ref "U17") (pin "6") (pinfunction "VCC_6") (pintype "passive"))
      (node (ref "U20") (pin "2") (pinfunction "VCC_2") (pintype "passive"))
      (node (ref "U21") (pin "2") (pinfunction "VCC_2") (pintype "passive"))
      (node (ref "U22") (pin "2") (pinfunction "VCC_2") (pintype "passive"))
      (node (ref "U23") (pin "2") (pinfunction "VCC_2") (pintype "passive"))
    )
    (net (code "52") (name "unconnected-(U15-ADBUS2-Pad18)") (class "Default")
      (node (ref "U15") (pin "18") (pinfunction "ADBUS2_18") (pintype "bidirectional+no_connect"))
    )
    (net (code "53") (name "unconnected-(U15-ADBUS3-Pad19)") (class "Default")
      (node (ref "U15") (pin "19") (pinfunction "ADBUS3_19") (pintype "bidirectional+no_connect"))
    )
    (net (code "54") (name "unconnected-(U15-ADBUS4-Pad21)") (class "Default")
      (node (ref "U15") (pin "21") (pinfunction "ADBUS4_21") (pintype "bidirectional+no_connect"))
    )
    (net (code "55") (name "unconnected-(U15-ADBUS5-Pad22)") (class "Default")
      (node (ref "U15") (pin "22") (pinfunction "ADBUS5_22") (pintype "bidirectional+no_connect"))
    )
    (net (code "56") (name "unconnected-(U15-ADBUS6-Pad23)") (class "Default")
      (node (ref "U15") (pin "23") (pinfunction "ADBUS6_23") (pintype "bidirectional+no_connect"))
    )
    (net (code "57") (name "unconnected-(U15-ADBUS7-Pad24)") (class "Default")
      (node (ref "U15") (pin "24") (pinfunction "ADBUS7_24") (pintype "bidirectional+no_connect"))
    )
    (net (code "58") (name "unconnected-(U15-BDBUS2-Pad28)") (class "Default")
      (node (ref "U15") (pin "28") (pinfunction "BDBUS2_28") (pintype "bidirectional+no_connect"))
    )
    (net (code "59") (name "unconnected-(U15-BDBUS3-Pad29)") (class "Default")
      (node (ref "U15") (pin "29") (pinfunction "BDBUS3_29") (pintype "bidirectional+no_connect"))
    )
    (net (code "60") (name "unconnected-(U15-BDBUS4-Pad30)") (class "Default")
      (node (ref "U15") (pin "30") (pinfunction "BDBUS4_30") (pintype "bidirectional+no_connect"))
    )
    (net (code "61") (name "unconnected-(U15-BDBUS5-Pad32)") (class "Default")
      (node (ref "U15") (pin "32") (pinfunction "BDBUS5_32") (pintype "bidirectional+no_connect"))
    )
    (net (code "62") (name "unconnected-(U15-BDBUS6-Pad33)") (class "Default")
      (node (ref "U15") (pin "33") (pinfunction "BDBUS6_33") (pintype "bidirectional+no_connect"))
    )
    (net (code "63") (name "unconnected-(U15-BDBUS7-Pad34)") (class "Default")
      (node (ref "U15") (pin "34") (pinfunction "BDBUS7_34") (pintype "bidirectional+no_connect"))
    )
    (net (code "64") (name "unconnected-(U15-CDBUS2-Pad40)") (class "Default")
      (node (ref "U15") (pin "40") (pinfunction "CDBUS2_40") (pintype "bidirectional+no_connect"))
    )
    (net (code "65") (name "unconnected-(U15-CDBUS3-Pad41)") (class "Default")
      (node (ref "U15") (pin "41") (pinfunction "CDBUS3_41") (pintype "bidirectional+no_connect"))
    )
    (net (code "66") (name "unconnected-(U15-CDBUS4-Pad43)") (class "Default")
      (node (ref "U15") (pin "43") (pinfunction "CDBUS4_43") (pintype "bidirectional+no_connect"))
    )
    (net (code "67") (name "unconnected-(U15-CDBUS5-Pad44)") (class "Default")
      (node (ref "U15") (pin "44") (pinfunction "CDBUS5_44") (pintype "bidirectional+no_connect"))
    )
    (net (code "68") (name "unconnected-(U15-CDBUS6-Pad45)") (class "Default")
      (node (ref "U15") (pin "45") (pinfunction "CDBUS6_45") (pintype "bidirectional+no_connect"))
    )
    (net (code "69") (name "unconnected-(U15-CDBUS7-Pad46)") (class "Default")
      (node (ref "U15") (pin "46") (pinfunction "CDBUS7_46") (pintype "bidirectional+no_connect"))
    )
    (net (code "70") (name "unconnected-(U15-DDBUS2-Pad53)") (class "Default")
      (node (ref "U15") (pin "53") (pinfunction "DDBUS2_53") (pintype "bidirectional+no_connect"))
    )
    (net (code "71") (name "unconnected-(U15-DDBUS3-Pad54)") (class "Default")
      (node (ref "U15") (pin "54") (pinfunction "DDBUS3_54") (pintype "bidirectional+no_connect"))
    )
    (net (code "72") (name "unconnected-(U15-DDBUS4-Pad55)") (class "Default")
      (node (ref "U15") (pin "55") (pinfunction "DDBUS4_55") (pintype "bidirectional+no_connect"))
    )
    (net (code "73") (name "unconnected-(U15-DDBUS5-Pad57)") (class "Default")
      (node (ref "U15") (pin "57") (pinfunction "DDBUS5_57") (pintype "bidirectional+no_connect"))
    )
    (net (code "74") (name "unconnected-(U15-DDBUS6-Pad58)") (class "Default")
      (node (ref "U15") (pin "58") (pinfunction "DDBUS6_58") (pintype "bidirectional+no_connect"))
    )
    (net (code "75") (name "unconnected-(U15-DDBUS7-Pad59)") (class "Default")
      (node (ref "U15") (pin "59") (pinfunction "DDBUS7_59") (pintype "bidirectional+no_connect"))
    )
    (net (code "76") (name "unconnected-(U15-SUSPEND#-Pad36)") (class "Default")
      (node (ref "U15") (pin "36") (pinfunction "SUSPEND#_36") (pintype "output+no_connect"))
    )
    (net (code "77") (name "unconnected-(U16-QH'-Pad9)") (class "Default")
      (node (ref "U16") (pin "9") (pinfunction "QH'_9") (pintype "passive+no_connect"))
    )
  )
)
